# 555-PWM-Motor-Speed-Controller-alt.net
KiCad netlist of a schematic drawn in EAGLE
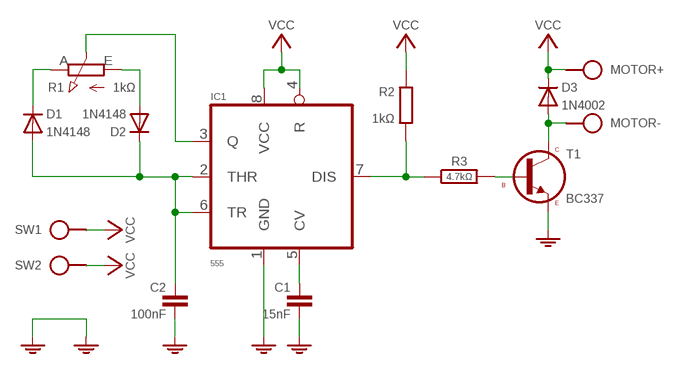
[diagram p0: schematic, sheet 1]

(export (version "E")
  (design (tool "Eeschema 10.0.6"))
  (components
    (comp (ref "C1")
      (value "15nF")
      (footprint "eagle-import:C050-020X036_V")
      (libsource (lib "eagle-import") (part "C050-020X036/V"))
    )
    (comp (ref "C2")
      (value "100nF")
      (footprint "eagle-import:C025-015X024_V")
      (libsource (lib "eagle-import") (part "C025-015X024/V"))
    )
    (comp (ref "D1")
      (value "1N4148")
      (footprint "eagle-import:DO34-5V")
      (libsource (lib "eagle-import") (part "DIODE34-5V"))
    )
    (comp (ref "D2")
      (value "1N4148")
      (footprint "eagle-import:DO34-5-V")
      (libsource (lib "eagle-import") (part "DIODE34-5-V"))
    )
    (comp (ref "D3")
      (value "1N4002")
      (footprint "eagle-import:DO34-5V")
      (libsource (lib "eagle-import") (part "DIODE34-5V"))
    )
    (comp (ref "IC1")
      (value "555")
      (footprint "eagle-import:DIL08")
      (libsource (lib "eagle-import") (part "555_ALT3"))
    )
    (comp (ref "MOTOR")
      (value "SPAD+-+-")
      (footprint "eagle-import:SPAD+-")
      (libsource (lib "eagle-import") (part "SPAD+-+-"))
    )
    (comp (ref "PWR")
      (value "VCC_GNDR")
      (footprint "eagle-import:SPAD+-")
      (libsource (lib "eagle-import") (part "VCC_GNDR"))
    )
    (comp (ref "R1")
      (value "1kΩ")
      (footprint "eagle-import:CONN-3P_H")
      (libsource (lib "eagle-import") (part "POT-H-3P/H"))
    )
    (comp (ref "R2")
      (value "1kΩ")
      (footprint "eagle-import:0204_10-V")
      (libsource (lib "eagle-import") (part "R0204/10-V"))
    )
    (comp (ref "R3")
      (value "4.7kΩ")
      (footprint "eagle-import:0204_10-V")
      (libsource (lib "eagle-import") (part "R-H0204/10-V"))
    )
    (comp (ref "SW1")
      (value "SPAD-1")
      (footprint "eagle-import:SPAD")
      (libsource (lib "eagle-import") (part "SPAD-1"))
    )
    (comp (ref "SW2")
      (value "SPAD-1")
      (footprint "eagle-import:SPAD")
      (libsource (lib "eagle-import") (part "SPAD-1"))
    )
    (comp (ref "T1")
      (value "BC337")
      (footprint "eagle-import:TO92-CBE")
      (libsource (lib "eagle-import") (part "BC337CBE"))
    )
  )
  (nets
    (net (code "1") (name "GND") (class "Default")
      (node (ref "C1") (pin "2") (pinfunction "2_2") (pintype "passive"))
      (node (ref "C2") (pin "2") (pinfunction "2_2") (pintype "passive"))
      (node (ref "IC1") (pin "1") (pinfunction "GND_1") (pintype "power_in"))
      (node (ref "PWR") (pin "1") (pinfunction "GND_1") (pintype "power_in"))
      (node (ref "T1") (pin "3") (pinfunction "E_3") (pintype "passive"))
    )
    (net (code "2") (name "Net-(IC1-CV)") (class "Default")
      (node (ref "C1") (pin "1") (pinfunction "1_1") (pintype "passive"))
      (node (ref "IC1") (pin "5") (pinfunction "CV_5") (pintype "input"))
    )
    (net (code "3") (name "Net-(IC1-DIS)") (class "Default")
      (node (ref "IC1") (pin "7") (pinfunction "DIS_7") (pintype "passive"))
      (node (ref "R2") (pin "2") (pinfunction "1_2") (pintype "passive"))
      (node (ref "R3") (pin "1") (pinfunction "1_1") (pintype "passive"))
    )
    (net (code "4") (name "Net-(IC1-Q)") (class "Default")
      (node (ref "IC1") (pin "3") (pinfunction "Q_3") (pintype "output"))
      (node (ref "R1") (pin "2") (pinfunction "S_2") (pintype "passive"))
    )
    (net (code "5") (name "Net-(IC1-THR)") (class "Default")
      (node (ref "C2") (pin "1") (pinfunction "1_1") (pintype "passive"))
      (node (ref "D1") (pin "A") (pinfunction "A_A") (pintype "passive"))
      (node (ref "D2") (pin "C") (pinfunction "C_C") (pintype "passive"))
      (node (ref "IC1") (pin "2") (pinfunction "THR_2") (pintype "input"))
      (node (ref "IC1") (pin "6") (pinfunction "TR_6") (pintype "input"))
    )
    (net (code "6") (name "Net-(MOTORB-P$1)") (class "Default")
      (node (ref "D3") (pin "A") (pinfunction "A_A") (pintype "passive"))
      (node (ref "MOTOR") (pin "1") (pinfunction "P$1_1") (pintype "passive"))
      (node (ref "T1") (pin "1") (pinfunction "C_1") (pintype "passive"))
    )
    (net (code "7") (name "Net-(PWRA-VCC)") (class "Default")
      (node (ref "PWR") (pin "2") (pinfunction "VCC_2") (pintype "power_in"))
      (node (ref "SW1") (pin "1") (pinfunction "P$1_1") (pintype "passive"))
    )
    (net (code "8") (name "Net-(R1-A)") (class "Default")
      (node (ref "D2") (pin "A") (pinfunction "A_A") (pintype "passive"))
      (node (ref "R1") (pin "1") (pinfunction "A_1") (pintype "passive"))
    )
    (net (code "9") (name "Net-(R1-E)") (class "Default")
      (node (ref "D1") (pin "C") (pinfunction "C_C") (pintype "passive"))
      (node (ref "R1") (pin "3") (pinfunction "E_3") (pintype "passive"))
    )
    (net (code "10") (name "Net-(T1-B)") (class "Default")
      (node (ref "R3") (pin "2") (pinfunction "2_2") (pintype "passive"))
      (node (ref "T1") (pin "2") (pinfunction "B_2") (pintype "passive"))
    )
    (net (code "11") (name "VCC") (class "Default")
      (node (ref "D3") (pin "C") (pinfunction "C_C") (pintype "passive"))
      (node (ref "IC1") (pin "4") (pinfunction "R_4") (pintype "input"))
      (node (ref "IC1") (pin "8") (pinfunction "VCC_8") (pintype "power_in"))
      (node (ref "MOTOR") (pin "2") (pinfunction "P$1_2") (pintype "passive"))
      (node (ref "R2") (pin "1") (pinfunction "2_1") (pintype "passive"))
      (node (ref "SW2") (pin "1") (pinfunction "P$1_1") (pintype "passive"))
    )
  )
)
